# BBB_Proto_Cape.net
KiCad netlist of a schematic drawn in EAGLE
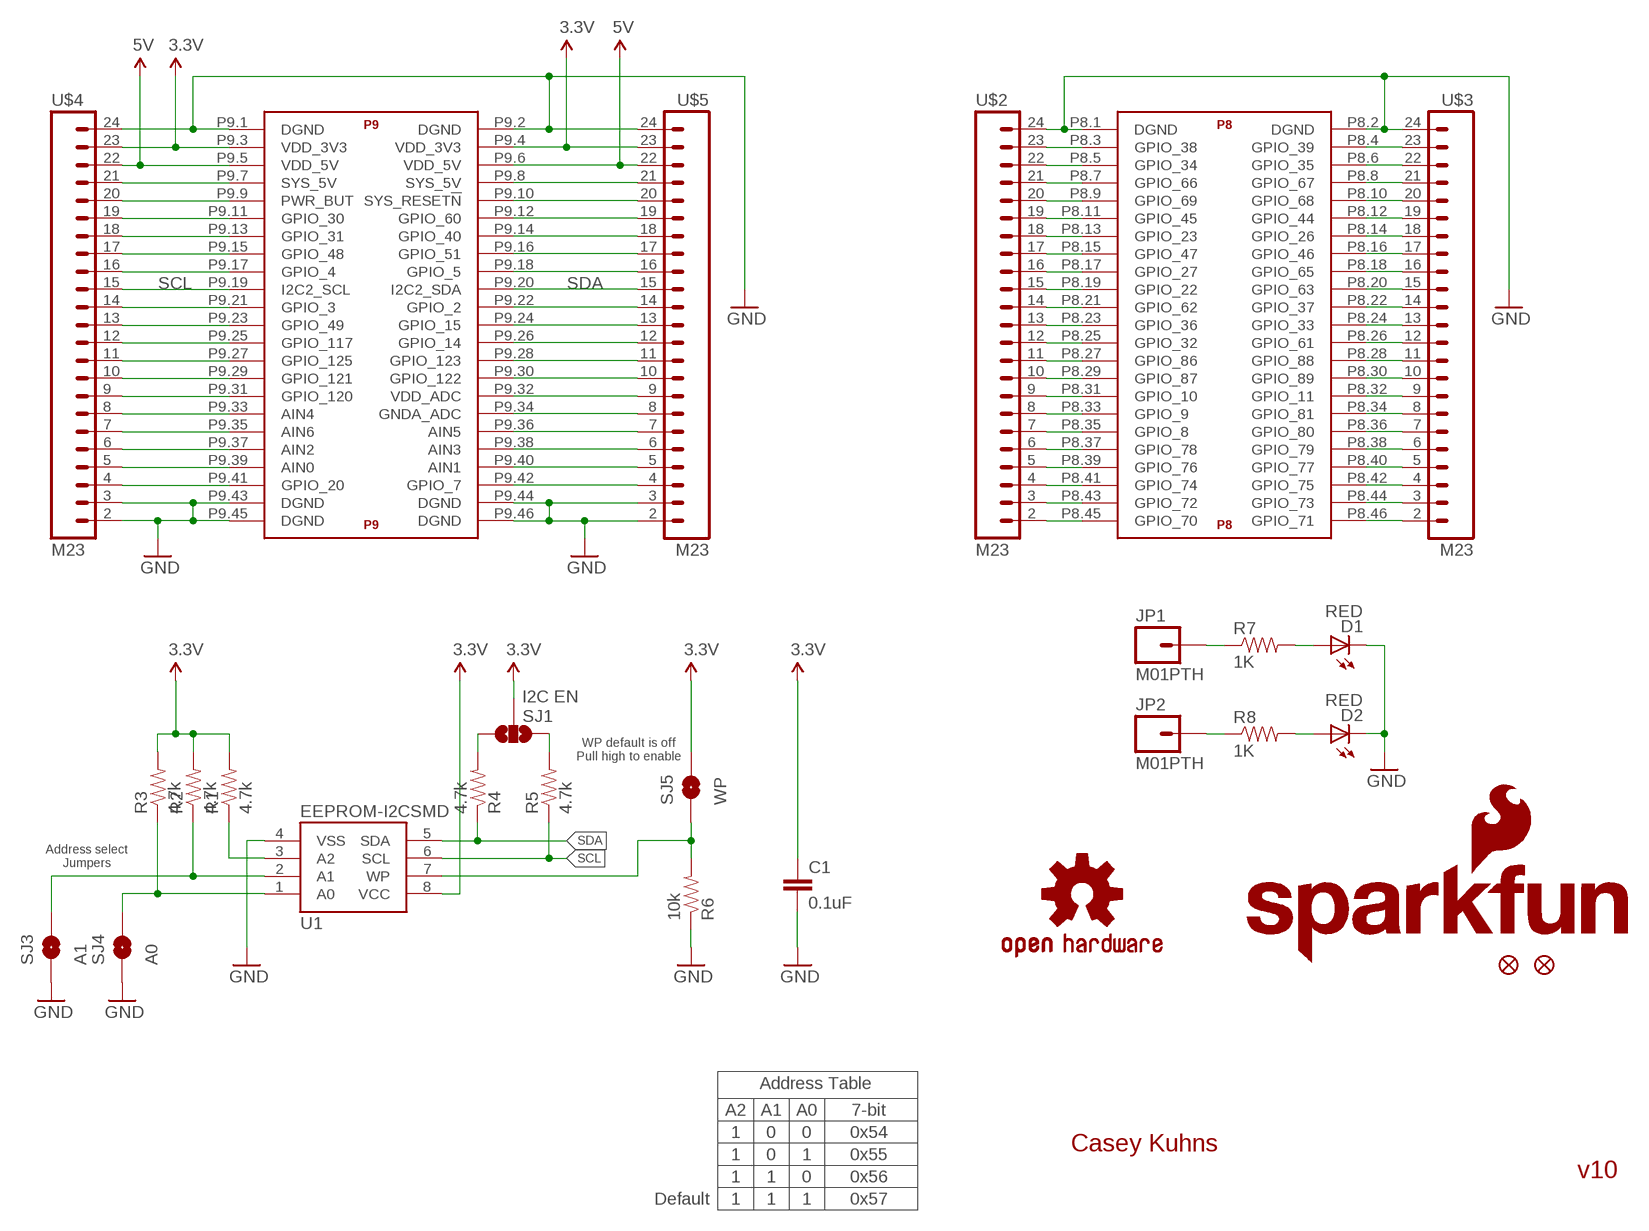
[diagram p0: schematic, sheet 1]

(export (version "E")
  (design (tool "Eeschema 10.0.6"))
  (components
    (comp (ref "C1")
      (value "0.1uF")
      (footprint "eagle-import:0603-CAP")
      (libsource (lib "eagle-import") (part "0.1UF-25V(+80/-20%)(0603)"))
    )
    (comp (ref "D1")
      (value "RED")
      (footprint "eagle-import:LED-0603")
      (libsource (lib "eagle-import") (part "LED-RED0603"))
    )
    (comp (ref "D2")
      (value "RED")
      (footprint "eagle-import:LED-0603")
      (libsource (lib "eagle-import") (part "LED-RED0603"))
    )
    (comp (ref "FID1")
      (value "FIDUCIAL1X2")
      (footprint "eagle-import:FIDUCIAL-1X2")
      (libsource (lib "eagle-import") (part "FIDUCIAL1X2"))
    )
    (comp (ref "FID2")
      (value "FIDUCIAL1X2")
      (footprint "eagle-import:FIDUCIAL-1X2")
      (libsource (lib "eagle-import") (part "FIDUCIAL1X2"))
    )
    (comp (ref "JP1")
      (value "M01PTH")
      (footprint "eagle-import:1X01")
      (libsource (lib "eagle-import") (part "M01PTH"))
    )
    (comp (ref "JP2")
      (value "M01PTH")
      (footprint "eagle-import:1X01")
      (libsource (lib "eagle-import") (part "M01PTH"))
    )
    (comp (ref "LOGO2")
      (value "OSHW-LOGOS")
      (footprint "eagle-import:OSHW-LOGO-S")
      (libsource (lib "eagle-import") (part "OSHW-LOGOS"))
    )
    (comp (ref "LOGO3")
      (value "SFE_LOGO_NAME_FLAME.1_INCH")
      (footprint "eagle-import:SFE_LOGO_NAME_FLAME_.1")
      (libsource (lib "eagle-import") (part "SFE_LOGO_NAME_FLAME.1_INCH"))
    )
    (comp (ref "R1")
      (value "4.7k")
      (footprint "eagle-import:0603")
      (libsource (lib "eagle-import") (part "4.7KOHM1/10W1%(0603)"))
    )
    (comp (ref "R2")
      (value "4.7k")
      (footprint "eagle-import:0603")
      (libsource (lib "eagle-import") (part "4.7KOHM1/10W1%(0603)"))
    )
    (comp (ref "R3")
      (value "4.7k")
      (footprint "eagle-import:0603")
      (libsource (lib "eagle-import") (part "4.7KOHM1/10W1%(0603)"))
    )
    (comp (ref "R4")
      (value "4.7k")
      (footprint "eagle-import:0603")
      (fields (field (name "PROD_ID") "RES-07857"))
      (libsource (lib "eagle-import") (part "4.7KOHM1/10W1%(0603)"))
    )
    (comp (ref "R5")
      (value "4.7k")
      (footprint "eagle-import:0603")
      (fields (field (name "PROD_ID") "RES-07857"))
      (libsource (lib "eagle-import") (part "4.7KOHM1/10W1%(0603)"))
    )
    (comp (ref "R6")
      (value "10k")
      (footprint "eagle-import:0603-RES")
      (libsource (lib "eagle-import") (part "10KOHM1/10W1%(0603)0603"))
    )
    (comp (ref "R7")
      (value "1K")
      (footprint "eagle-import:0603-RES")
      (libsource (lib "eagle-import") (part "1KOHM1/10W1%(0603)"))
    )
    (comp (ref "R8")
      (value "1K")
      (footprint "eagle-import:0603-RES")
      (libsource (lib "eagle-import") (part "1KOHM1/10W1%(0603)"))
    )
    (comp (ref "SJ1")
      (value "I2C EN")
      (footprint "eagle-import:SJ_3_PASTE1&2&3")
      (libsource (lib "eagle-import") (part "SOLDERJUMPER_2WAYPASTE1&2&3"))
    )
    (comp (ref "SJ3")
      (value "A1")
      (footprint "eagle-import:SJ_2S-NO")
      (libsource (lib "eagle-import") (part "SOLDERJUMPERNO"))
    )
    (comp (ref "SJ4")
      (value "A0")
      (footprint "eagle-import:SJ_2S-NO")
      (libsource (lib "eagle-import") (part "SOLDERJUMPERNO"))
    )
    (comp (ref "SJ5")
      (value "WP")
      (footprint "eagle-import:SJ_2S-NO")
      (libsource (lib "eagle-import") (part "SOLDERJUMPERNO"))
    )
    (comp (ref "U$1")
      (value "BEAGLE_BONE_BLACK_CAPE")
      (footprint "eagle-import:BEAGLE_BONE_BLACK_CAPE")
      (libsource (lib "eagle-import") (part "BEAGLE_BONE_BLACK_CAPE"))
    )
    (comp (ref "U$2")
      (value "M23")
      (footprint "eagle-import:1X23")
      (libsource (lib "eagle-import") (part "M23"))
    )
    (comp (ref "U$3")
      (value "M23")
      (footprint "eagle-import:1X23")
      (libsource (lib "eagle-import") (part "M23"))
    )
    (comp (ref "U$4")
      (value "M23")
      (footprint "eagle-import:1X23")
      (libsource (lib "eagle-import") (part "M23"))
    )
    (comp (ref "U$5")
      (value "M23")
      (footprint "eagle-import:1X23")
      (libsource (lib "eagle-import") (part "M23"))
    )
    (comp (ref "U1")
      (value "EEPROM-I2CSMD")
      (footprint "eagle-import:SO08")
      (libsource (lib "eagle-import") (part "EEPROM-I2CSMD"))
    )
  )
  (nets
    (net (code "1") (name "3.3V") (class "Default")
      (node (ref "C1") (pin "1") (pinfunction "1_1") (pintype "passive"))
      (node (ref "R1") (pin "2") (pinfunction "2_2") (pintype "passive"))
      (node (ref "R2") (pin "2") (pinfunction "2_2") (pintype "passive"))
      (node (ref "R3") (pin "2") (pinfunction "2_2") (pintype "passive"))
      (node (ref "SJ1") (pin "2") (pinfunction "2_2") (pintype "passive"))
      (node (ref "SJ5") (pin "2") (pinfunction "2_2") (pintype "passive"))
      (node (ref "U$1") (pin "P9.3") (pinfunction "VDD_3V3_P9.3") (pintype "bidirectional"))
      (node (ref "U$1") (pin "P9.4") (pinfunction "VDD_3V3_P9.4") (pintype "bidirectional"))
      (node (ref "U$4") (pin "23") (pinfunction "23_23") (pintype "passive"))
      (node (ref "U$5") (pin "23") (pinfunction "23_23") (pintype "passive"))
      (node (ref "U1") (pin "8") (pinfunction "VCC_8") (pintype "power_in"))
    )
    (net (code "2") (name "5V") (class "Default")
      (node (ref "U$1") (pin "P9.5") (pinfunction "VDD_5V_P9.5") (pintype "bidirectional"))
      (node (ref "U$1") (pin "P9.6") (pinfunction "VDD_5V_P9.6") (pintype "bidirectional"))
      (node (ref "U$4") (pin "22") (pinfunction "22_22") (pintype "passive"))
      (node (ref "U$5") (pin "22") (pinfunction "22_22") (pintype "passive"))
    )
    (net (code "3") (name "GND") (class "Default")
      (node (ref "C1") (pin "2") (pinfunction "2_2") (pintype "passive"))
      (node (ref "D1") (pin "C") (pinfunction "C_C") (pintype "passive"))
      (node (ref "D2") (pin "C") (pinfunction "C_C") (pintype "passive"))
      (node (ref "R6") (pin "1") (pinfunction "1_1") (pintype "passive"))
      (node (ref "SJ3") (pin "1") (pinfunction "1_1") (pintype "passive"))
      (node (ref "SJ4") (pin "1") (pinfunction "1_1") (pintype "passive"))
      (node (ref "U$1") (pin "P8.1") (pinfunction "DGND_P8.1") (pintype "bidirectional"))
      (node (ref "U$1") (pin "P8.2") (pinfunction "DGND_P8.2") (pintype "bidirectional"))
      (node (ref "U$1") (pin "P9.1") (pinfunction "DGND_P9.1") (pintype "bidirectional"))
      (node (ref "U$1") (pin "P9.2") (pinfunction "DGND_P9.2") (pintype "bidirectional"))
      (node (ref "U$1") (pin "P9.43") (pinfunction "DGND_P9.43") (pintype "bidirectional"))
      (node (ref "U$1") (pin "P9.44") (pinfunction "DGND_P9.44") (pintype "bidirectional"))
      (node (ref "U$1") (pin "P9.45") (pinfunction "DGND_P9.45") (pintype "bidirectional"))
      (node (ref "U$1") (pin "P9.46") (pinfunction "DGND_P9.46") (pintype "bidirectional"))
      (node (ref "U$2") (pin "24") (pinfunction "24_24") (pintype "passive"))
      (node (ref "U$3") (pin "24") (pinfunction "24_24") (pintype "passive"))
      (node (ref "U$4") (pin "2") (pinfunction "2_2") (pintype "passive"))
      (node (ref "U$4") (pin "24") (pinfunction "24_24") (pintype "passive"))
      (node (ref "U$4") (pin "3") (pinfunction "3_3") (pintype "passive"))
      (node (ref "U$5") (pin "2") (pinfunction "2_2") (pintype "passive"))
      (node (ref "U$5") (pin "24") (pinfunction "24_24") (pintype "passive"))
      (node (ref "U$5") (pin "3") (pinfunction "3_3") (pintype "passive"))
      (node (ref "U1") (pin "4") (pinfunction "VSS_4") (pintype "power_in"))
    )
    (net (code "4") (name "Net-(D1-PadA)") (class "Default")
      (node (ref "D1") (pin "A") (pinfunction "A_A") (pintype "passive"))
      (node (ref "R7") (pin "2") (pinfunction "2_2") (pintype "passive"))
    )
    (net (code "5") (name "Net-(D2-PadA)") (class "Default")
      (node (ref "D2") (pin "A") (pinfunction "A_A") (pintype "passive"))
      (node (ref "R8") (pin "2") (pinfunction "2_2") (pintype "passive"))
    )
    (net (code "6") (name "Net-(JP1-Pad1)") (class "Default")
      (node (ref "JP1") (pin "1") (pinfunction "1_1") (pintype "passive"))
      (node (ref "R7") (pin "1") (pinfunction "1_1") (pintype "passive"))
    )
    (net (code "7") (name "Net-(JP2-Pad1)") (class "Default")
      (node (ref "JP2") (pin "1") (pinfunction "1_1") (pintype "passive"))
      (node (ref "R8") (pin "1") (pinfunction "1_1") (pintype "passive"))
    )
    (net (code "8") (name "Net-(R4-Pad2)") (class "Default")
      (node (ref "R4") (pin "2") (pinfunction "2_2") (pintype "passive"))
      (node (ref "SJ1") (pin "3") (pinfunction "3_3") (pintype "passive"))
    )
    (net (code "9") (name "Net-(R5-Pad2)") (class "Default")
      (node (ref "R5") (pin "2") (pinfunction "2_2") (pintype "passive"))
      (node (ref "SJ1") (pin "1") (pinfunction "1_1") (pintype "passive"))
    )
    (net (code "10") (name "Net-(U$1A-GPIO_8)") (class "Default")
      (node (ref "U$1") (pin "P8.35") (pinfunction "GPIO_8_P8.35") (pintype "bidirectional"))
      (node (ref "U$2") (pin "7") (pinfunction "7_7") (pintype "passive"))
    )
    (net (code "11") (name "Net-(U$1A-GPIO_9)") (class "Default")
      (node (ref "U$1") (pin "P8.33") (pinfunction "GPIO_9_P8.33") (pintype "bidirectional"))
      (node (ref "U$2") (pin "8") (pinfunction "8_8") (pintype "passive"))
    )
    (net (code "12") (name "Net-(U$1A-GPIO_10)") (class "Default")
      (node (ref "U$1") (pin "P8.31") (pinfunction "GPIO_10_P8.31") (pintype "bidirectional"))
      (node (ref "U$2") (pin "9") (pinfunction "9_9") (pintype "passive"))
    )
    (net (code "13") (name "Net-(U$1A-GPIO_11)") (class "Default")
      (node (ref "U$1") (pin "P8.32") (pinfunction "GPIO_11_P8.32") (pintype "bidirectional"))
      (node (ref "U$3") (pin "9") (pinfunction "9_9") (pintype "passive"))
    )
    (net (code "14") (name "Net-(U$1A-GPIO_22)") (class "Default")
      (node (ref "U$1") (pin "P8.19") (pinfunction "GPIO_22_P8.19") (pintype "bidirectional"))
      (node (ref "U$2") (pin "15") (pinfunction "15_15") (pintype "passive"))
    )
    (net (code "15") (name "Net-(U$1A-GPIO_23)") (class "Default")
      (node (ref "U$1") (pin "P8.13") (pinfunction "GPIO_23_P8.13") (pintype "bidirectional"))
      (node (ref "U$2") (pin "18") (pinfunction "18_18") (pintype "passive"))
    )
    (net (code "16") (name "Net-(U$1A-GPIO_26)") (class "Default")
      (node (ref "U$1") (pin "P8.14") (pinfunction "GPIO_26_P8.14") (pintype "bidirectional"))
      (node (ref "U$3") (pin "18") (pinfunction "18_18") (pintype "passive"))
    )
    (net (code "17") (name "Net-(U$1A-GPIO_27)") (class "Default")
      (node (ref "U$1") (pin "P8.17") (pinfunction "GPIO_27_P8.17") (pintype "bidirectional"))
      (node (ref "U$2") (pin "16") (pinfunction "16_16") (pintype "passive"))
    )
    (net (code "18") (name "Net-(U$1A-GPIO_32)") (class "Default")
      (node (ref "U$1") (pin "P8.25") (pinfunction "GPIO_32_P8.25") (pintype "bidirectional"))
      (node (ref "U$2") (pin "12") (pinfunction "12_12") (pintype "passive"))
    )
    (net (code "19") (name "Net-(U$1A-GPIO_33)") (class "Default")
      (node (ref "U$1") (pin "P8.24") (pinfunction "GPIO_33_P8.24") (pintype "bidirectional"))
      (node (ref "U$3") (pin "13") (pinfunction "13_13") (pintype "passive"))
    )
    (net (code "20") (name "Net-(U$1A-GPIO_34)") (class "Default")
      (node (ref "U$1") (pin "P8.5") (pinfunction "GPIO_34_P8.5") (pintype "bidirectional"))
      (node (ref "U$2") (pin "22") (pinfunction "22_22") (pintype "passive"))
    )
    (net (code "21") (name "Net-(U$1A-GPIO_35)") (class "Default")
      (node (ref "U$1") (pin "P8.6") (pinfunction "GPIO_35_P8.6") (pintype "bidirectional"))
      (node (ref "U$3") (pin "22") (pinfunction "22_22") (pintype "passive"))
    )
    (net (code "22") (name "Net-(U$1A-GPIO_36)") (class "Default")
      (node (ref "U$1") (pin "P8.23") (pinfunction "GPIO_36_P8.23") (pintype "bidirectional"))
      (node (ref "U$2") (pin "13") (pinfunction "13_13") (pintype "passive"))
    )
    (net (code "23") (name "Net-(U$1A-GPIO_37)") (class "Default")
      (node (ref "U$1") (pin "P8.22") (pinfunction "GPIO_37_P8.22") (pintype "bidirectional"))
      (node (ref "U$3") (pin "14") (pinfunction "14_14") (pintype "passive"))
    )
    (net (code "24") (name "Net-(U$1A-GPIO_38)") (class "Default")
      (node (ref "U$1") (pin "P8.3") (pinfunction "GPIO_38_P8.3") (pintype "bidirectional"))
      (node (ref "U$2") (pin "23") (pinfunction "23_23") (pintype "passive"))
    )
    (net (code "25") (name "Net-(U$1A-GPIO_39)") (class "Default")
      (node (ref "U$1") (pin "P8.4") (pinfunction "GPIO_39_P8.4") (pintype "bidirectional"))
      (node (ref "U$3") (pin "23") (pinfunction "23_23") (pintype "passive"))
    )
    (net (code "26") (name "Net-(U$1A-GPIO_44)") (class "Default")
      (node (ref "U$1") (pin "P8.12") (pinfunction "GPIO_44_P8.12") (pintype "bidirectional"))
      (node (ref "U$3") (pin "19") (pinfunction "19_19") (pintype "passive"))
    )
    (net (code "27") (name "Net-(U$1A-GPIO_45)") (class "Default")
      (node (ref "U$1") (pin "P8.11") (pinfunction "GPIO_45_P8.11") (pintype "bidirectional"))
      (node (ref "U$2") (pin "19") (pinfunction "19_19") (pintype "passive"))
    )
    (net (code "28") (name "Net-(U$1A-GPIO_46)") (class "Default")
      (node (ref "U$1") (pin "P8.16") (pinfunction "GPIO_46_P8.16") (pintype "bidirectional"))
      (node (ref "U$3") (pin "17") (pinfunction "17_17") (pintype "passive"))
    )
    (net (code "29") (name "Net-(U$1A-GPIO_47)") (class "Default")
      (node (ref "U$1") (pin "P8.15") (pinfunction "GPIO_47_P8.15") (pintype "bidirectional"))
      (node (ref "U$2") (pin "17") (pinfunction "17_17") (pintype "passive"))
    )
    (net (code "30") (name "Net-(U$1A-GPIO_61)") (class "Default")
      (node (ref "U$1") (pin "P8.26") (pinfunction "GPIO_61_P8.26") (pintype "bidirectional"))
      (node (ref "U$3") (pin "12") (pinfunction "12_12") (pintype "passive"))
    )
    (net (code "31") (name "Net-(U$1A-GPIO_62)") (class "Default")
      (node (ref "U$1") (pin "P8.21") (pinfunction "GPIO_62_P8.21") (pintype "bidirectional"))
      (node (ref "U$2") (pin "14") (pinfunction "14_14") (pintype "passive"))
    )
    (net (code "32") (name "Net-(U$1A-GPIO_63)") (class "Default")
      (node (ref "U$1") (pin "P8.20") (pinfunction "GPIO_63_P8.20") (pintype "bidirectional"))
      (node (ref "U$3") (pin "15") (pinfunction "15_15") (pintype "passive"))
    )
    (net (code "33") (name "Net-(U$1A-GPIO_65)") (class "Default")
      (node (ref "U$1") (pin "P8.18") (pinfunction "GPIO_65_P8.18") (pintype "bidirectional"))
      (node (ref "U$3") (pin "16") (pinfunction "16_16") (pintype "passive"))
    )
    (net (code "34") (name "Net-(U$1A-GPIO_66)") (class "Default")
      (node (ref "U$1") (pin "P8.7") (pinfunction "GPIO_66_P8.7") (pintype "bidirectional"))
      (node (ref "U$2") (pin "21") (pinfunction "21_21") (pintype "passive"))
    )
    (net (code "35") (name "Net-(U$1A-GPIO_67)") (class "Default")
      (node (ref "U$1") (pin "P8.8") (pinfunction "GPIO_67_P8.8") (pintype "bidirectional"))
      (node (ref "U$3") (pin "21") (pinfunction "21_21") (pintype "passive"))
    )
    (net (code "36") (name "Net-(U$1A-GPIO_68)") (class "Default")
      (node (ref "U$1") (pin "P8.10") (pinfunction "GPIO_68_P8.10") (pintype "bidirectional"))
      (node (ref "U$3") (pin "20") (pinfunction "20_20") (pintype "passive"))
    )
    (net (code "37") (name "Net-(U$1A-GPIO_69)") (class "Default")
      (node (ref "U$1") (pin "P8.9") (pinfunction "GPIO_69_P8.9") (pintype "bidirectional"))
      (node (ref "U$2") (pin "20") (pinfunction "20_20") (pintype "passive"))
    )
    (net (code "38") (name "Net-(U$1A-GPIO_70)") (class "Default")
      (node (ref "U$1") (pin "P8.45") (pinfunction "GPIO_70_P8.45") (pintype "bidirectional"))
      (node (ref "U$2") (pin "2") (pinfunction "2_2") (pintype "passive"))
    )
    (net (code "39") (name "Net-(U$1A-GPIO_71)") (class "Default")
      (node (ref "U$1") (pin "P8.46") (pinfunction "GPIO_71_P8.46") (pintype "bidirectional"))
      (node (ref "U$3") (pin "2") (pinfunction "2_2") (pintype "passive"))
    )
    (net (code "40") (name "Net-(U$1A-GPIO_72)") (class "Default")
      (node (ref "U$1") (pin "P8.43") (pinfunction "GPIO_72_P8.43") (pintype "bidirectional"))
      (node (ref "U$2") (pin "3") (pinfunction "3_3") (pintype "passive"))
    )
    (net (code "41") (name "Net-(U$1A-GPIO_73)") (class "Default")
      (node (ref "U$1") (pin "P8.44") (pinfunction "GPIO_73_P8.44") (pintype "bidirectional"))
      (node (ref "U$3") (pin "3") (pinfunction "3_3") (pintype "passive"))
    )
    (net (code "42") (name "Net-(U$1A-GPIO_74)") (class "Default")
      (node (ref "U$1") (pin "P8.41") (pinfunction "GPIO_74_P8.41") (pintype "bidirectional"))
      (node (ref "U$2") (pin "4") (pinfunction "4_4") (pintype "passive"))
    )
    (net (code "43") (name "Net-(U$1A-GPIO_75)") (class "Default")
      (node (ref "U$1") (pin "P8.42") (pinfunction "GPIO_75_P8.42") (pintype "bidirectional"))
      (node (ref "U$3") (pin "4") (pinfunction "4_4") (pintype "passive"))
    )
    (net (code "44") (name "Net-(U$1A-GPIO_76)") (class "Default")
      (node (ref "U$1") (pin "P8.39") (pinfunction "GPIO_76_P8.39") (pintype "bidirectional"))
      (node (ref "U$2") (pin "5") (pinfunction "5_5") (pintype "passive"))
    )
    (net (code "45") (name "Net-(U$1A-GPIO_77)") (class "Default")
      (node (ref "U$1") (pin "P8.40") (pinfunction "GPIO_77_P8.40") (pintype "bidirectional"))
      (node (ref "U$3") (pin "5") (pinfunction "5_5") (pintype "passive"))
    )
    (net (code "46") (name "Net-(U$1A-GPIO_78)") (class "Default")
      (node (ref "U$1") (pin "P8.37") (pinfunction "GPIO_78_P8.37") (pintype "bidirectional"))
      (node (ref "U$2") (pin "6") (pinfunction "6_6") (pintype "passive"))
    )
    (net (code "47") (name "Net-(U$1A-GPIO_79)") (class "Default")
      (node (ref "U$1") (pin "P8.38") (pinfunction "GPIO_79_P8.38") (pintype "bidirectional"))
      (node (ref "U$3") (pin "6") (pinfunction "6_6") (pintype "passive"))
    )
    (net (code "48") (name "Net-(U$1A-GPIO_80)") (class "Default")
      (node (ref "U$1") (pin "P8.36") (pinfunction "GPIO_80_P8.36") (pintype "bidirectional"))
      (node (ref "U$3") (pin "7") (pinfunction "7_7") (pintype "passive"))
    )
    (net (code "49") (name "Net-(U$1A-GPIO_81)") (class "Default")
      (node (ref "U$1") (pin "P8.34") (pinfunction "GPIO_81_P8.34") (pintype "bidirectional"))
      (node (ref "U$3") (pin "8") (pinfunction "8_8") (pintype "passive"))
    )
    (net (code "50") (name "Net-(U$1A-GPIO_86)") (class "Default")
      (node (ref "U$1") (pin "P8.27") (pinfunction "GPIO_86_P8.27") (pintype "bidirectional"))
      (node (ref "U$2") (pin "11") (pinfunction "11_11") (pintype "passive"))
    )
    (net (code "51") (name "Net-(U$1A-GPIO_87)") (class "Default")
      (node (ref "U$1") (pin "P8.29") (pinfunction "GPIO_87_P8.29") (pintype "bidirectional"))
      (node (ref "U$2") (pin "10") (pinfunction "10_10") (pintype "passive"))
    )
    (net (code "52") (name "Net-(U$1A-GPIO_88)") (class "Default")
      (node (ref "U$1") (pin "P8.28") (pinfunction "GPIO_88_P8.28") (pintype "bidirectional"))
      (node (ref "U$3") (pin "11") (pinfunction "11_11") (pintype "passive"))
    )
    (net (code "53") (name "Net-(U$1A-GPIO_89)") (class "Default")
      (node (ref "U$1") (pin "P8.30") (pinfunction "GPIO_89_P8.30") (pintype "bidirectional"))
      (node (ref "U$3") (pin "10") (pinfunction "10_10") (pintype "passive"))
    )
    (net (code "54") (name "Net-(U$1B-AIN0)") (class "Default")
      (node (ref "U$1") (pin "P9.39") (pinfunction "AIN0_P9.39") (pintype "bidirectional"))
      (node (ref "U$4") (pin "5") (pinfunction "5_5") (pintype "passive"))
    )
    (net (code "55") (name "Net-(U$1B-AIN1)") (class "Default")
      (node (ref "U$1") (pin "P9.40") (pinfunction "AIN1_P9.40") (pintype "bidirectional"))
      (node (ref "U$5") (pin "5") (pinfunction "5_5") (pintype "passive"))
    )
    (net (code "56") (name "Net-(U$1B-AIN2)") (class "Default")
      (node (ref "U$1") (pin "P9.37") (pinfunction "AIN2_P9.37") (pintype "bidirectional"))
      (node (ref "U$4") (pin "6") (pinfunction "6_6") (pintype "passive"))
    )
    (net (code "57") (name "Net-(U$1B-AIN3)") (class "Default")
      (node (ref "U$1") (pin "P9.38") (pinfunction "AIN3_P9.38") (pintype "bidirectional"))
      (node (ref "U$5") (pin "6") (pinfunction "6_6") (pintype "passive"))
    )
    (net (code "58") (name "Net-(U$1B-AIN4)") (class "Default")
      (node (ref "U$1") (pin "P9.33") (pinfunction "AIN4_P9.33") (pintype "bidirectional"))
      (node (ref "U$4") (pin "8") (pinfunction "8_8") (pintype "passive"))
    )
    (net (code "59") (name "Net-(U$1B-AIN5)") (class "Default")
      (node (ref "U$1") (pin "P9.36") (pinfunction "AIN5_P9.36") (pintype "bidirectional"))
      (node (ref "U$5") (pin "7") (pinfunction "7_7") (pintype "passive"))
    )
    (net (code "60") (name "Net-(U$1B-AIN6)") (class "Default")
      (node (ref "U$1") (pin "P9.35") (pinfunction "AIN6_P9.35") (pintype "bidirectional"))
      (node (ref "U$4") (pin "7") (pinfunction "7_7") (pintype "passive"))
    )
    (net (code "61") (name "Net-(U$1B-GNDA_ADC)") (class "Default")
      (node (ref "U$1") (pin "P9.34") (pinfunction "GNDA_ADC_P9.34") (pintype "bidirectional"))
      (node (ref "U$5") (pin "8") (pinfunction "8_8") (pintype "passive"))
    )
    (net (code "62") (name "Net-(U$1B-GPIO_2)") (class "Default")
      (node (ref "U$1") (pin "P9.22") (pinfunction "GPIO_2_P9.22") (pintype "bidirectional"))
      (node (ref "U$5") (pin "14") (pinfunction "14_14") (pintype "passive"))
    )
    (net (code "63") (name "Net-(U$1B-GPIO_3)") (class "Default")
      (node (ref "U$1") (pin "P9.21") (pinfunction "GPIO_3_P9.21") (pintype "bidirectional"))
      (node (ref "U$4") (pin "14") (pinfunction "14_14") (pintype "passive"))
    )
    (net (code "64") (name "Net-(U$1B-GPIO_4)") (class "Default")
      (node (ref "U$1") (pin "P9.17") (pinfunction "GPIO_4_P9.17") (pintype "bidirectional"))
      (node (ref "U$4") (pin "16") (pinfunction "16_16") (pintype "passive"))
    )
    (net (code "65") (name "Net-(U$1B-GPIO_5)") (class "Default")
      (node (ref "U$1") (pin "P9.18") (pinfunction "GPIO_5_P9.18") (pintype "bidirectional"))
      (node (ref "U$5") (pin "16") (pinfunction "16_16") (pintype "passive"))
    )
    (net (code "66") (name "Net-(U$1B-GPIO_7)") (class "Default")
      (node (ref "U$1") (pin "P9.42") (pinfunction "GPIO_7_P9.42") (pintype "bidirectional"))
      (node (ref "U$5") (pin "4") (pinfunction "4_4") (pintype "passive"))
    )
    (net (code "67") (name "Net-(U$1B-GPIO_14)") (class "Default")
      (node (ref "U$1") (pin "P9.26") (pinfunction "GPIO_14_P9.26") (pintype "bidirectional"))
      (node (ref "U$5") (pin "12") (pinfunction "12_12") (pintype "passive"))
    )
    (net (code "68") (name "Net-(U$1B-GPIO_15)") (class "Default")
      (node (ref "U$1") (pin "P9.24") (pinfunction "GPIO_15_P9.24") (pintype "bidirectional"))
      (node (ref "U$5") (pin "13") (pinfunction "13_13") (pintype "passive"))
    )
    (net (code "69") (name "Net-(U$1B-GPIO_20)") (class "Default")
      (node (ref "U$1") (pin "P9.41") (pinfunction "GPIO_20_P9.41") (pintype "bidirectional"))
      (node (ref "U$4") (pin "4") (pinfunction "4_4") (pintype "passive"))
    )
    (net (code "70") (name "Net-(U$1B-GPIO_30)") (class "Default")
      (node (ref "U$1") (pin "P9.11") (pinfunction "GPIO_30_P9.11") (pintype "bidirectional"))
      (node (ref "U$4") (pin "19") (pinfunction "19_19") (pintype "passive"))
    )
    (net (code "71") (name "Net-(U$1B-GPIO_31)") (class "Default")
      (node (ref "U$1") (pin "P9.13") (pinfunction "GPIO_31_P9.13") (pintype "bidirectional"))
      (node (ref "U$4") (pin "18") (pinfunction "18_18") (pintype "passive"))
    )
    (net (code "72") (name "Net-(U$1B-GPIO_40)") (class "Default")
      (node (ref "U$1") (pin "P9.14") (pinfunction "GPIO_40_P9.14") (pintype "bidirectional"))
      (node (ref "U$5") (pin "18") (pinfunction "18_18") (pintype "passive"))
    )
    (net (code "73") (name "Net-(U$1B-GPIO_48)") (class "Default")
      (node (ref "U$1") (pin "P9.15") (pinfunction "GPIO_48_P9.15") (pintype "bidirectional"))
      (node (ref "U$4") (pin "17") (pinfunction "17_17") (pintype "passive"))
    )
    (net (code "74") (name "Net-(U$1B-GPIO_49)") (class "Default")
      (node (ref "U$1") (pin "P9.23") (pinfunction "GPIO_49_P9.23") (pintype "bidirectional"))
      (node (ref "U$4") (pin "13") (pinfunction "13_13") (pintype "passive"))
    )
    (net (code "75") (name "Net-(U$1B-GPIO_51)") (class "Default")
      (node (ref "U$1") (pin "P9.16") (pinfunction "GPIO_51_P9.16") (pintype "bidirectional"))
      (node (ref "U$5") (pin "17") (pinfunction "17_17") (pintype "passive"))
    )
    (net (code "76") (name "Net-(U$1B-GPIO_60)") (class "Default")
      (node (ref "U$1") (pin "P9.12") (pinfunction "GPIO_60_P9.12") (pintype "bidirectional"))
      (node (ref "U$5") (pin "19") (pinfunction "19_19") (pintype "passive"))
    )
    (net (code "77") (name "Net-(U$1B-GPIO_117)") (class "Default")
      (node (ref "U$1") (pin "P9.25") (pinfunction "GPIO_117_P9.25") (pintype "bidirectional"))
      (node (ref "U$4") (pin "12") (pinfunction "12_12") (pintype "passive"))
    )
    (net (code "78") (name "Net-(U$1B-GPIO_120)") (class "Default")
      (node (ref "U$1") (pin "P9.31") (pinfunction "GPIO_120_P9.31") (pintype "bidirectional"))
      (node (ref "U$4") (pin "9") (pinfunction "9_9") (pintype "passive"))
    )
    (net (code "79") (name "Net-(U$1B-GPIO_121)") (class "Default")
      (node (ref "U$1") (pin "P9.29") (pinfunction "GPIO_121_P9.29") (pintype "bidirectional"))
      (node (ref "U$4") (pin "10") (pinfunction "10_10") (pintype "passive"))
    )
    (net (code "80") (name "Net-(U$1B-GPIO_122)") (class "Default")
      (node (ref "U$1") (pin "P9.30") (pinfunction "GPIO_122_P9.30") (pintype "bidirectional"))
      (node (ref "U$5") (pin "10") (pinfunction "10_10") (pintype "passive"))
    )
    (net (code "81") (name "Net-(U$1B-GPIO_123)") (class "Default")
      (node (ref "U$1") (pin "P9.28") (pinfunction "GPIO_123_P9.28") (pintype "bidirectional"))
      (node (ref "U$5") (pin "11") (pinfunction "11_11") (pintype "passive"))
    )
    (net (code "82") (name "Net-(U$1B-GPIO_125)") (class "Default")
      (node (ref "U$1") (pin "P9.27") (pinfunction "GPIO_125_P9.27") (pintype "bidirectional"))
      (node (ref "U$4") (pin "11") (pinfunction "11_11") (pintype "passive"))
    )
    (net (code "83") (name "Net-(U$1B-PWR_BUT)") (class "Default")
      (node (ref "U$1") (pin "P9.9") (pinfunction "PWR_BUT_P9.9") (pintype "bidirectional"))
      (node (ref "U$4") (pin "20") (pinfunction "20_20") (pintype "passive"))
    )
    (net (code "84") (name "Net-(U$1B-SYS_5V-PadP9.7)") (class "Default")
      (node (ref "U$1") (pin "P9.7") (pinfunction "SYS_5V_P9.7") (pintype "bidirectional"))
      (node (ref "U$4") (pin "21") (pinfunction "21_21") (pintype "passive"))
    )
    (net (code "85") (name "Net-(U$1B-SYS_5V-PadP9.8)") (class "Default")
      (node (ref "U$1") (pin "P9.8") (pinfunction "SYS_5V_P9.8") (pintype "bidirectional"))
      (node (ref "U$5") (pin "21") (pinfunction "21_21") (pintype "passive"))
    )
    (net (code "86") (name "Net-(U$1B-SYS_RESET~{N})") (class "Default")
      (node (ref "U$1") (pin "P9.10") (pinfunction "SYS_RESET~{N}_P9.10") (pintype "bidirectional"))
      (node (ref "U$5") (pin "20") (pinfunction "20_20") (pintype "passive"))
    )
    (net (code "87") (name "Net-(U$1B-VDD_ADC)") (class "Default")
      (node (ref "U$1") (pin "P9.32") (pinfunction "VDD_ADC_P9.32") (pintype "bidirectional"))
      (node (ref "U$5") (pin "9") (pinfunction "9_9") (pintype "passive"))
    )
    (net (code "88") (name "Net-(U1-A0)") (class "Default")
      (node (ref "R3") (pin "1") (pinfunction "1_1") (pintype "passive"))
      (node (ref "SJ4") (pin "2") (pinfunction "2_2") (pintype "passive"))
      (node (ref "U1") (pin "1") (pinfunction "A0_1") (pintype "bidirectional"))
    )
    (net (code "89") (name "Net-(U1-A1)") (class "Default")
      (node (ref "R2") (pin "1") (pinfunction "1_1") (pintype "passive"))
      (node (ref "SJ3") (pin "2") (pinfunction "2_2") (pintype "passive"))
      (node (ref "U1") (pin "2") (pinfunction "A1_2") (pintype "bidirectional"))
    )
    (net (code "90") (name "Net-(U1-A2)") (class "Default")
      (node (ref "R1") (pin "1") (pinfunction "1_1") (pintype "passive"))
      (node (ref "U1") (pin "3") (pinfunction "A2_3") (pintype "bidirectional"))
    )
    (net (code "91") (name "Net-(U1-WP)") (class "Default")
      (node (ref "R6") (pin "2") (pinfunction "2_2") (pintype "passive"))
      (node (ref "SJ5") (pin "1") (pinfunction "1_1") (pintype "passive"))
      (node (ref "U1") (pin "7") (pinfunction "WP_7") (pintype "bidirectional"))
    )
    (net (code "92") (name "SCL") (class "Default")
      (node (ref "R5") (pin "1") (pinfunction "1_1") (pintype "passive"))
      (node (ref "U$1") (pin "P9.19") (pinfunction "I2C2_SCL_P9.19") (pintype "bidirectional"))
      (node (ref "U$4") (pin "15") (pinfunction "15_15") (pintype "passive"))
      (node (ref "U1") (pin "6") (pinfunction "SCL_6") (pintype "bidirectional"))
    )
    (net (code "93") (name "SDA") (class "Default")
      (node (ref "R4") (pin "1") (pinfunction "1_1") (pintype "passive"))
      (node (ref "U$1") (pin "P9.20") (pinfunction "I2C2_SDA_P9.20") (pintype "bidirectional"))
      (node (ref "U$5") (pin "15") (pinfunction "15_15") (pintype "passive"))
      (node (ref "U1") (pin "5") (pinfunction "SDA_5") (pintype "bidirectional"))
    )
  )
)
